# v6_config_io_16_17_21_22.net
KiCad netlist of a schematic drawn in Altium Designer
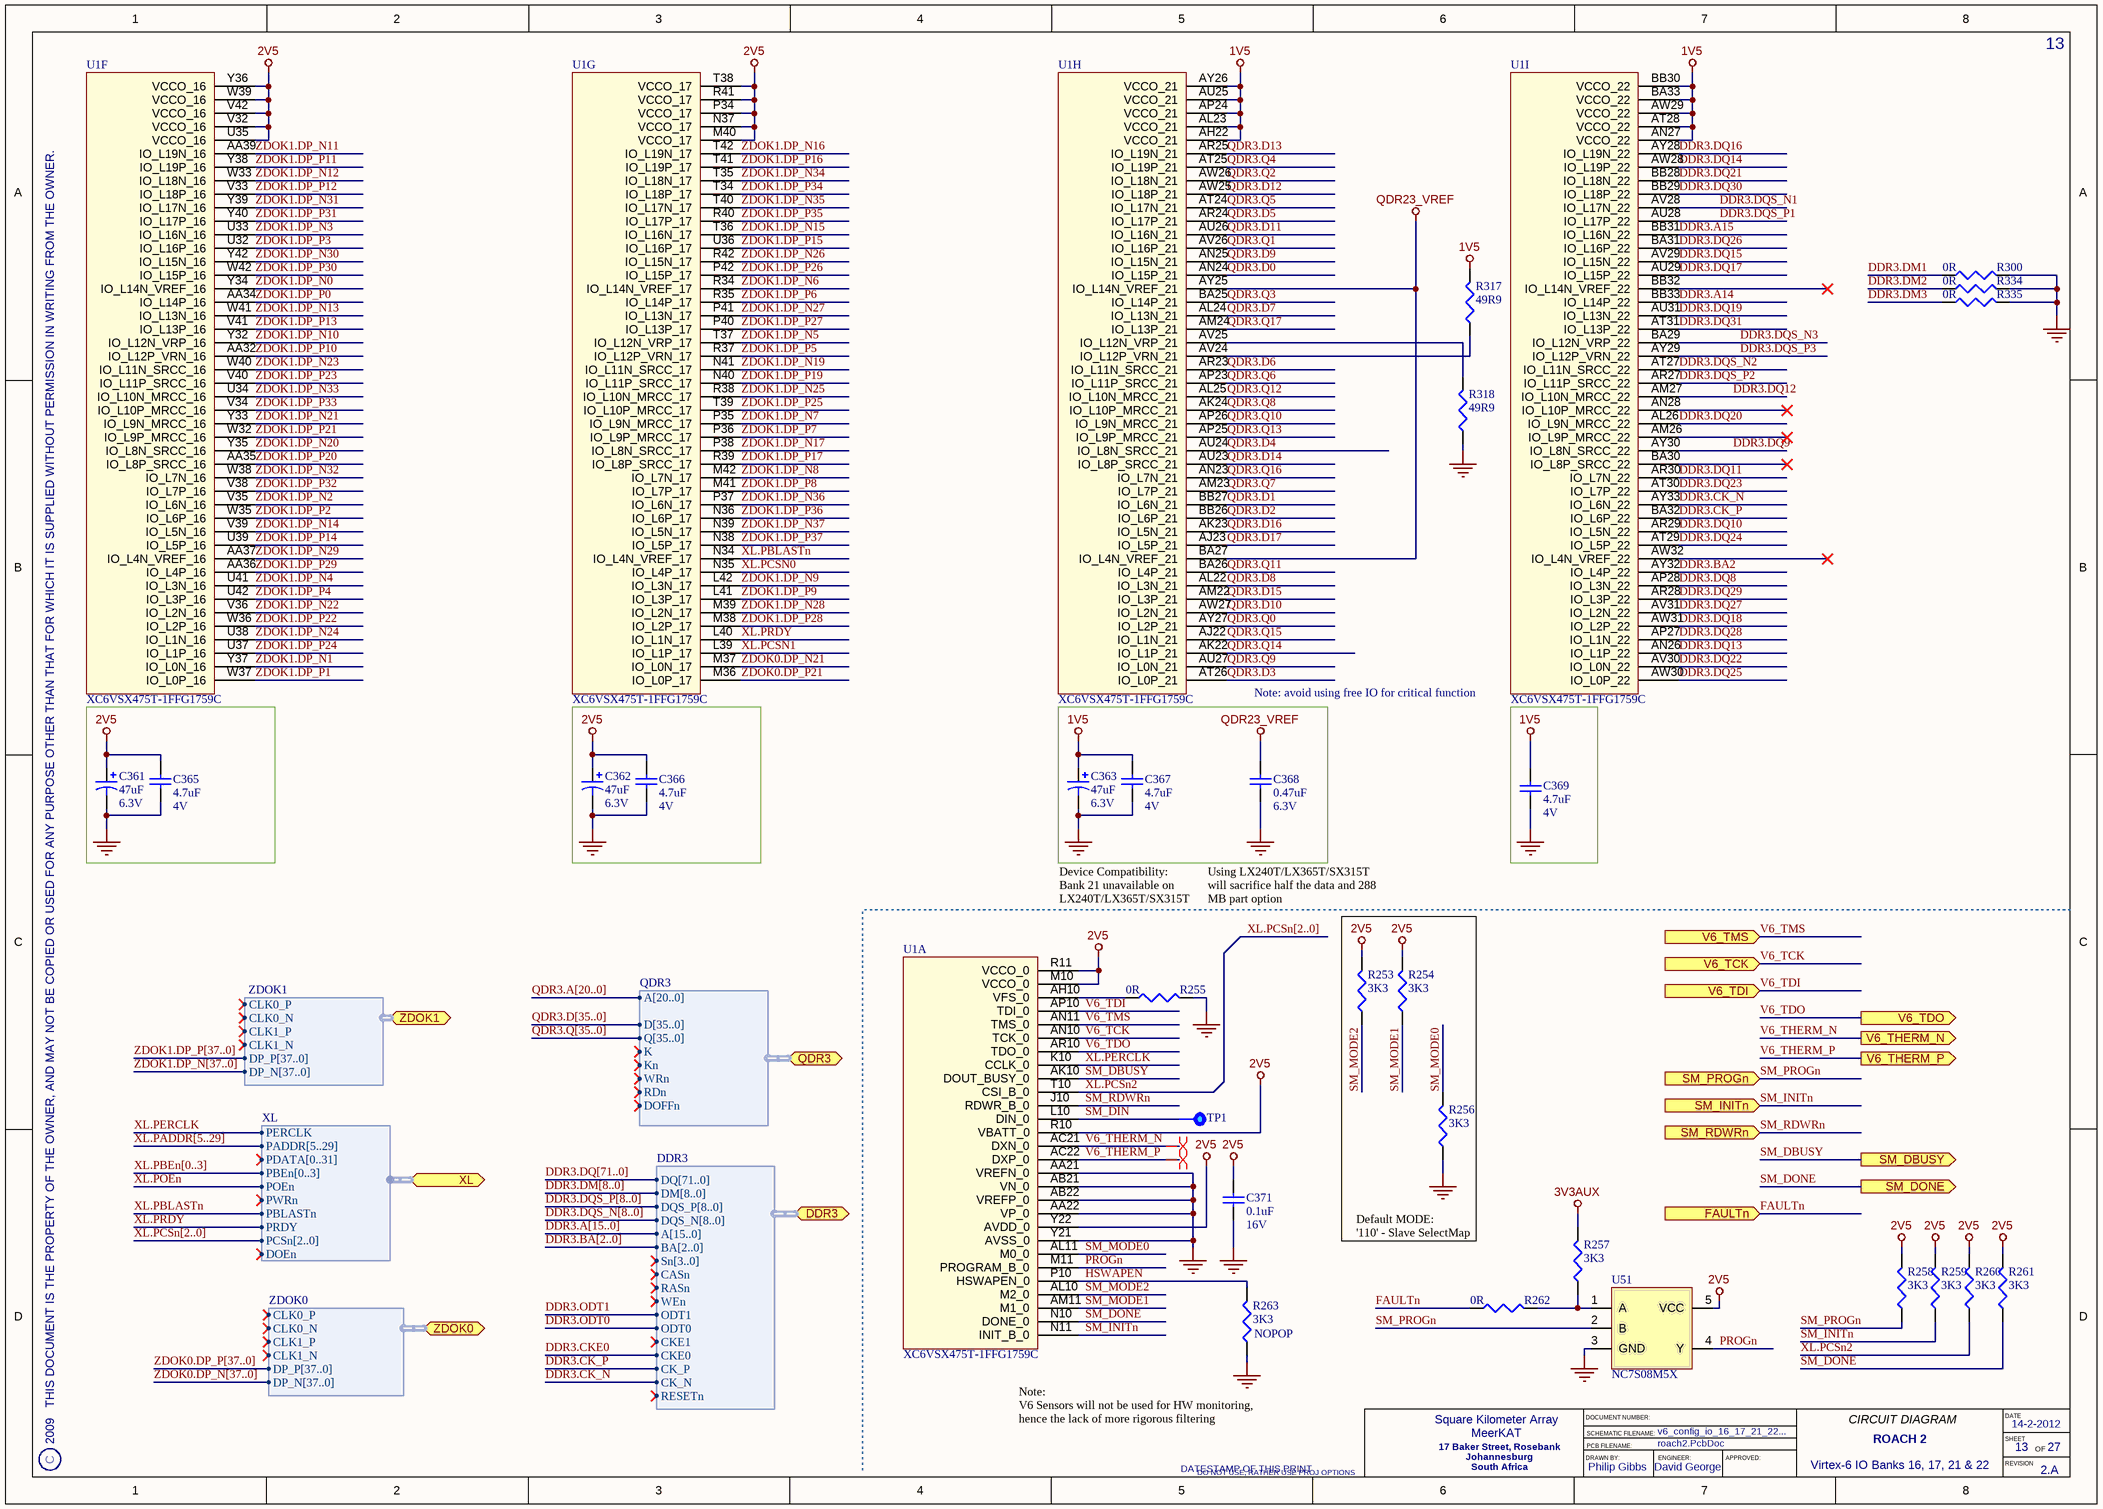
[diagram p0: v6_config_io_16_17_21_22.SchDoc]

(export (version "E")
  (design (tool "Eeschema 10.0.6"))
  (components
    (comp (ref "C361")
      (value "47uF")
      (footprint "CAPMP3528X120L")
      (description "47uF, Conductive Polymer Chip Capacitor")
      (fields
        (field (name "RATING") "6.3V")
        (field (name "MANUFACTURER") "KEMET")
        (field (name "PARTNUM") "T520T476M006ATE070")
      )
      (libsource (lib "altium_db") (part "CapPol"))
    )
    (comp (ref "C362")
      (value "47uF")
      (footprint "CAPMP3528X120L")
      (description "47uF, Conductive Polymer Chip Capacitor")
      (fields
        (field (name "RATING") "6.3V")
        (field (name "MANUFACTURER") "KEMET")
        (field (name "PARTNUM") "T520T476M006ATE070")
      )
      (libsource (lib "altium_db") (part "CapPol"))
    )
    (comp (ref "C363")
      (value "47uF")
      (footprint "CAPMP3528X120L")
      (description "47uF, Conductive Polymer Chip Capacitor")
      (fields
        (field (name "RATING") "6.3V")
        (field (name "MANUFACTURER") "KEMET")
        (field (name "PARTNUM") "T520T476M006ATE070")
      )
      (libsource (lib "altium_db") (part "CapPol"))
    )
    (comp (ref "C365")
      (value "4.7uF")
      (footprint "CAPC1005X60L")
      (description "4.7uF, Ceramic Capacitor")
      (fields
        (field (name "RATING") "4V")
        (field (name "MANUFACTURER") "MURATA")
        (field (name "PARTNUM") "AMK105BJ475MV-F")
      )
      (libsource (lib "altium_db") (part "CapStd"))
    )
    (comp (ref "C366")
      (value "4.7uF")
      (footprint "CAPC1005X60L")
      (description "4.7uF, Ceramic Capacitor")
      (fields
        (field (name "RATING") "4V")
        (field (name "MANUFACTURER") "MURATA")
        (field (name "PARTNUM") "AMK105BJ475MV-F")
      )
      (libsource (lib "altium_db") (part "CapStd"))
    )
    (comp (ref "C367")
      (value "4.7uF")
      (footprint "CAPC1005X60L")
      (description "4.7uF, Ceramic Capacitor")
      (fields
        (field (name "RATING") "4V")
        (field (name "MANUFACTURER") "MURATA")
        (field (name "PARTNUM") "AMK105BJ475MV-F")
      )
      (libsource (lib "altium_db") (part "CapStd"))
    )
    (comp (ref "C368")
      (value "0.47uF")
      (footprint "CAPC1005X55L")
      (description "0.47uF, Ceramic Capacitor")
      (fields
        (field (name "RATING") "6.3V")
        (field (name "MANUFACTURER") "MURATA")
        (field (name "PARTNUM") "GRM155R60J474KE19")
      )
      (libsource (lib "altium_db") (part "CapStd"))
    )
    (comp (ref "C369")
      (value "4.7uF")
      (footprint "CAPC1005X60L")
      (description "4.7uF, Ceramic Capacitor")
      (fields
        (field (name "RATING") "4V")
        (field (name "MANUFACTURER") "MURATA")
        (field (name "PARTNUM") "AMK105BJ475MV-F")
      )
      (libsource (lib "altium_db") (part "CapStd"))
    )
    (comp (ref "C371")
      (value "0.1uF")
      (footprint "CAPC1005X60L")
      (description "0.1uF, Ceramic Capacitor")
      (fields
        (field (name "RATING") "16V")
        (field (name "MANUFACTURER") "VENKEL")
        (field (name "PARTNUM") "C0402X7R160-104KN")
      )
      (libsource (lib "altium_db") (part "CapStd"))
    )
    (comp (ref "R253")
      (value "3K3")
      (footprint "RESC1005X40L")
      (description "3K3, 1.1mm x 0.5mm, Thick Film Resistor")
      (fields (field (name "MANUFACTURER") "ROYALOHM") (field (name "PARTNUM") "0402WGJ0332T1E"))
      (libsource (lib "altium_db") (part "ResStd"))
    )
    (comp (ref "R254")
      (value "3K3")
      (footprint "RESC1005X40L")
      (description "3K3, 1.1mm x 0.5mm, Thick Film Resistor")
      (fields (field (name "MANUFACTURER") "ROYALOHM") (field (name "PARTNUM") "0402WGJ0332T1E"))
      (libsource (lib "altium_db") (part "ResStd"))
    )
    (comp (ref "R255")
      (value "0R")
      (footprint "RESC1005X40L")
      (description "0R, 1.1mm x 0.5mm, Thick Film Resistor")
      (fields (field (name "MANUFACTURER") "ROYALOHM") (field (name "PARTNUM") "0402WG00000T1E"))
      (libsource (lib "altium_db") (part "ResStd"))
    )
    (comp (ref "R256")
      (value "3K3")
      (footprint "RESC1005X40L")
      (description "3K3, 1.1mm x 0.5mm, Thick Film Resistor")
      (fields (field (name "MANUFACTURER") "ROYALOHM") (field (name "PARTNUM") "0402WGJ0332T1E"))
      (libsource (lib "altium_db") (part "ResStd"))
    )
    (comp (ref "R257")
      (value "3K3")
      (footprint "RESC1005X40L")
      (description "3K3, 1.1mm x 0.5mm, Thick Film Resistor")
      (fields (field (name "MANUFACTURER") "ROYALOHM") (field (name "PARTNUM") "0402WGJ0332T1E"))
      (libsource (lib "altium_db") (part "ResStd"))
    )
    (comp (ref "R258")
      (value "3K3")
      (footprint "RESC1005X40L")
      (description "3K3, 1.1mm x 0.5mm, Thick Film Resistor")
      (fields (field (name "MANUFACTURER") "ROYALOHM") (field (name "PARTNUM") "0402WGJ0332T1E"))
      (libsource (lib "altium_db") (part "ResStd"))
    )
    (comp (ref "R259")
      (value "3K3")
      (footprint "RESC1005X40L")
      (description "3K3, 1.1mm x 0.5mm, Thick Film Resistor")
      (fields (field (name "MANUFACTURER") "ROYALOHM") (field (name "PARTNUM") "0402WGJ0332T1E"))
      (libsource (lib "altium_db") (part "ResStd"))
    )
    (comp (ref "R260")
      (value "3K3")
      (footprint "RESC1005X40L")
      (description "3K3, 1.1mm x 0.5mm, Thick Film Resistor")
      (fields (field (name "MANUFACTURER") "ROYALOHM") (field (name "PARTNUM") "0402WGJ0332T1E"))
      (libsource (lib "altium_db") (part "ResStd"))
    )
    (comp (ref "R261")
      (value "3K3")
      (footprint "RESC1005X40L")
      (description "3K3, 1.1mm x 0.5mm, Thick Film Resistor")
      (fields (field (name "MANUFACTURER") "ROYALOHM") (field (name "PARTNUM") "0402WGJ0332T1E"))
      (libsource (lib "altium_db") (part "ResStd"))
    )
    (comp (ref "R262")
      (value "0R")
      (footprint "RESC1005X40L")
      (description "0R, 1.1mm x 0.5mm, Thick Film Resistor")
      (fields (field (name "MANUFACTURER") "ROYALOHM") (field (name "PARTNUM") "0402WG00000T1E"))
      (libsource (lib "altium_db") (part "ResStd"))
    )
    (comp (ref "R263")
      (value "3K3")
      (footprint "RESC1005X40L")
      (description "3K3, 1.1mm x 0.5mm, Thick Film Resistor")
      (fields (field (name "MANUFACTURER") "ROYALOHM") (field (name "PARTNUM") "0402WGJ0332T1E"))
      (libsource (lib "altium_db") (part "ResStd"))
    )
    (comp (ref "R300")
      (value "0R")
      (footprint "RESC1005X40L")
      (description "0R, 1.1mm x 0.5mm, Thick Film Resistor")
      (fields (field (name "MANUFACTURER") "ROYALOHM") (field (name "PARTNUM") "0402WG00000T1E"))
      (libsource (lib "altium_db") (part "ResStd"))
    )
    (comp (ref "R317")
      (value "49R9")
      (footprint "RESC1005X40L")
      (description "49R9, 1.1mm x 0.5mm, Thick Film Resistor")
      (fields (field (name "MANUFACTURER") "ROYALOHM") (field (name "PARTNUM") "0402WGF499JT1E"))
      (libsource (lib "altium_db") (part "ResStd"))
    )
    (comp (ref "R318")
      (value "49R9")
      (footprint "RESC1005X40L")
      (description "49R9, 1.1mm x 0.5mm, Thick Film Resistor")
      (fields (field (name "MANUFACTURER") "ROYALOHM") (field (name "PARTNUM") "0402WGF499JT1E"))
      (libsource (lib "altium_db") (part "ResStd"))
    )
    (comp (ref "R334")
      (value "0R")
      (footprint "RESC1005X40L")
      (description "0R, 1.1mm x 0.5mm, Thick Film Resistor")
      (fields (field (name "MANUFACTURER") "ROYALOHM") (field (name "PARTNUM") "0402WG00000T1E"))
      (libsource (lib "altium_db") (part "ResStd"))
    )
    (comp (ref "R335")
      (value "0R")
      (footprint "RESC1005X40L")
      (description "0R, 1.1mm x 0.5mm, Thick Film Resistor")
      (fields (field (name "MANUFACTURER") "ROYALOHM") (field (name "PARTNUM") "0402WG00000T1E"))
      (libsource (lib "altium_db") (part "ResStd"))
    )
    (comp (ref "TP1")
      (value "Testpoint")
      (footprint "TP100")
      (description "1mm Diameter, through-hole, Circular Test-point")
      (libsource (lib "altium_db") (part "Testpoint"))
    )
    (comp (ref "U1")
      (value "XC6VSX475T-1FFG1759C")
      (footprint "FFG1759")
      (description "Virtex-6 475SXT 1760-pin FPGA")
      (fields (field (name "MANUFACTURER") "Xilinx"))
      (libsource (lib "altium_db") (part "XC6VSX475T-1FFG1759C"))
    )
    (comp (ref "U51")
      (value "NC7S08M5X")
      (footprint "SOT23-5")
      (description "TinyLogic® HS 2-Input AND Gate")
      (fields (field (name "MANUFACTURER") "Fairchild Semiconductor"))
      (libsource (lib "altium_db") (part "NC7S08"))
    )
  )
  (nets
    (net (code "185") (name "/DDR3.A14") (class "Default")
      (node (ref "U1") (pin "BB33") (pinfunction "IO_L14P_22_BB33") (pintype "passive"))
    )
    (net (code "186") (name "/DDR3.A15") (class "Default")
      (node (ref "U1") (pin "BB31") (pinfunction "IO_L16N_22_BB31") (pintype "passive"))
    )
    (net (code "188") (name "/DDR3.BA2") (class "Default")
      (node (ref "U1") (pin "AY32") (pinfunction "IO_L4P_22_AY32") (pintype "passive"))
    )
    (net (code "191") (name "/DDR3.CK_N") (class "Default")
      (node (ref "U1") (pin "AY33") (pinfunction "IO_L6N_22_AY33") (pintype "passive"))
    )
    (net (code "192") (name "/DDR3.CK_P") (class "Default")
      (node (ref "U1") (pin "BA32") (pinfunction "IO_L6P_22_BA32") (pintype "passive"))
    )
    (net (code "193") (name "/DDR3.DM1") (class "Default")
      (node (ref "R300") (pin "1") (pinfunction "1_1") (pintype "passive"))
    )
    (net (code "194") (name "/DDR3.DM2") (class "Default")
      (node (ref "R334") (pin "1") (pinfunction "1_1") (pintype "passive"))
    )
    (net (code "195") (name "/DDR3.DM3") (class "Default")
      (node (ref "R335") (pin "1") (pinfunction "1_1") (pintype "passive"))
    )
    (net (code "197") (name "/DDR3.DQ8") (class "Default")
      (node (ref "U1") (pin "AP28") (pinfunction "IO_L3N_22_AP28") (pintype "passive"))
    )
    (net (code "198") (name "/DDR3.DQ9") (class "Default")
      (node (ref "U1") (pin "AY30") (pinfunction "IO_L8N_SRCC_22_AY30") (pintype "passive"))
    )
    (net (code "199") (name "/DDR3.DQ10") (class "Default")
      (node (ref "U1") (pin "AR29") (pinfunction "IO_L5N_22_AR29") (pintype "passive"))
    )
    (net (code "200") (name "/DDR3.DQ11") (class "Default")
      (node (ref "U1") (pin "AR30") (pinfunction "IO_L7N_22_AR30") (pintype "passive"))
    )
    (net (code "201") (name "/DDR3.DQ12") (class "Default")
      (node (ref "U1") (pin "AM27") (pinfunction "IO_L10N_MRCC_22_AM27") (pintype "passive"))
    )
    (net (code "202") (name "/DDR3.DQ13") (class "Default")
      (node (ref "U1") (pin "AN26") (pinfunction "IO_L1P_22_AN26") (pintype "passive"))
    )
    (net (code "203") (name "/DDR3.DQ14") (class "Default")
      (node (ref "U1") (pin "AW28") (pinfunction "IO_L19P_22_AW28") (pintype "passive"))
    )
    (net (code "204") (name "/DDR3.DQ15") (class "Default")
      (node (ref "U1") (pin "AV29") (pinfunction "IO_L15N_22_AV29") (pintype "passive"))
    )
    (net (code "205") (name "/DDR3.DQ16") (class "Default")
      (node (ref "U1") (pin "AY28") (pinfunction "IO_L19N_22_AY28") (pintype "passive"))
    )
    (net (code "206") (name "/DDR3.DQ17") (class "Default")
      (node (ref "U1") (pin "AU29") (pinfunction "IO_L15P_22_AU29") (pintype "passive"))
    )
    (net (code "207") (name "/DDR3.DQ18") (class "Default")
      (node (ref "U1") (pin "AW31") (pinfunction "IO_L2P_22_AW31") (pintype "passive"))
    )
    (net (code "208") (name "/DDR3.DQ19") (class "Default")
      (node (ref "U1") (pin "AU31") (pinfunction "IO_L13N_22_AU31") (pintype "passive"))
    )
    (net (code "209") (name "/DDR3.DQ20") (class "Default")
      (node (ref "U1") (pin "AL26") (pinfunction "IO_L9N_MRCC_22_AL26") (pintype "passive"))
    )
    (net (code "210") (name "/DDR3.DQ21") (class "Default")
      (node (ref "U1") (pin "BB28") (pinfunction "IO_L18N_22_BB28") (pintype "passive"))
    )
    (net (code "211") (name "/DDR3.DQ22") (class "Default")
      (node (ref "U1") (pin "AV30") (pinfunction "IO_L0N_22_AV30") (pintype "passive"))
    )
    (net (code "212") (name "/DDR3.DQ23") (class "Default")
      (node (ref "U1") (pin "AT30") (pinfunction "IO_L7P_22_AT30") (pintype "passive"))
    )
    (net (code "213") (name "/DDR3.DQ24") (class "Default")
      (node (ref "U1") (pin "AT29") (pinfunction "IO_L5P_22_AT29") (pintype "passive"))
    )
    (net (code "214") (name "/DDR3.DQ25") (class "Default")
      (node (ref "U1") (pin "AW30") (pinfunction "IO_L0P_22_AW30") (pintype "passive"))
    )
    (net (code "215") (name "/DDR3.DQ26") (class "Default")
      (node (ref "U1") (pin "BA31") (pinfunction "IO_L16P_22_BA31") (pintype "passive"))
    )
    (net (code "216") (name "/DDR3.DQ27") (class "Default")
      (node (ref "U1") (pin "AV31") (pinfunction "IO_L2N_22_AV31") (pintype "passive"))
    )
    (net (code "217") (name "/DDR3.DQ28") (class "Default")
      (node (ref "U1") (pin "AP27") (pinfunction "IO_L1N_22_AP27") (pintype "passive"))
    )
    (net (code "218") (name "/DDR3.DQ29") (class "Default")
      (node (ref "U1") (pin "AR28") (pinfunction "IO_L3P_22_AR28") (pintype "passive"))
    )
    (net (code "219") (name "/DDR3.DQ30") (class "Default")
      (node (ref "U1") (pin "BB29") (pinfunction "IO_L18P_22_BB29") (pintype "passive"))
    )
    (net (code "220") (name "/DDR3.DQ31") (class "Default")
      (node (ref "U1") (pin "AT31") (pinfunction "IO_L13P_22_AT31") (pintype "passive"))
    )
    (net (code "221") (name "/DDR3.DQS_N1") (class "Default")
      (node (ref "U1") (pin "AV28") (pinfunction "IO_L17N_22_AV28") (pintype "passive"))
    )
    (net (code "222") (name "/DDR3.DQS_N2") (class "Default")
      (node (ref "U1") (pin "AT27") (pinfunction "IO_L11N_SRCC_22_AT27") (pintype "passive"))
    )
    (net (code "223") (name "/DDR3.DQS_N3") (class "Default")
      (node (ref "U1") (pin "BA29") (pinfunction "IO_L12N_VRP_22_BA29") (pintype "passive"))
    )
    (net (code "225") (name "/DDR3.DQS_P1") (class "Default")
      (node (ref "U1") (pin "AU28") (pinfunction "IO_L17P_22_AU28") (pintype "passive"))
    )
    (net (code "226") (name "/DDR3.DQS_P2") (class "Default")
      (node (ref "U1") (pin "AR27") (pinfunction "IO_L11P_SRCC_22_AR27") (pintype "passive"))
    )
    (net (code "227") (name "/DDR3.DQS_P3") (class "Default")
      (node (ref "U1") (pin "AY29") (pinfunction "IO_L12P_VRN_22_AY29") (pintype "passive"))
    )
    (net (code "232") (name "/FAULTn") (class "Default")
      (node (ref "R262") (pin "1") (pinfunction "1_1") (pintype "passive"))
    )
    (net (code "233") (name "/HSWAPEN") (class "Default")
      (node (ref "R263") (pin "2") (pinfunction "2_2") (pintype "passive"))
      (node (ref "U1") (pin "P10") (pinfunction "HSWAPEN_0_P10") (pintype "passive"))
    )
    (net (code "234") (name "/PROGn") (class "Default")
      (node (ref "U1") (pin "M11") (pinfunction "PROGRAM_B_0_M11") (pintype "passive"))
      (node (ref "U51") (pin "4") (pinfunction "Y_4") (pintype "passive"))
    )
    (net (code "236") (name "/QDR3.D0") (class "Default")
      (node (ref "U1") (pin "AN24") (pinfunction "IO_L15P_21_AN24") (pintype "passive"))
    )
    (net (code "237") (name "/QDR3.D1") (class "Default")
      (node (ref "U1") (pin "BB27") (pinfunction "IO_L6N_21_BB27") (pintype "passive"))
    )
    (net (code "238") (name "/QDR3.D2") (class "Default")
      (node (ref "U1") (pin "BB26") (pinfunction "IO_L6P_21_BB26") (pintype "passive"))
    )
    (net (code "239") (name "/QDR3.D3") (class "Default")
      (node (ref "U1") (pin "AT26") (pinfunction "IO_L0P_21_AT26") (pintype "passive"))
    )
    (net (code "240") (name "/QDR3.D4") (class "Default")
      (node (ref "U1") (pin "AU24") (pinfunction "IO_L8N_SRCC_21_AU24") (pintype "passive"))
    )
    (net (code "241") (name "/QDR3.D5") (class "Default")
      (node (ref "U1") (pin "AR24") (pinfunction "IO_L17P_21_AR24") (pintype "passive"))
    )
    (net (code "242") (name "/QDR3.D6") (class "Default")
      (node (ref "U1") (pin "AR23") (pinfunction "IO_L11N_SRCC_21_AR23") (pintype "passive"))
    )
    (net (code "243") (name "/QDR3.D7") (class "Default")
      (node (ref "U1") (pin "AL24") (pinfunction "IO_L13N_21_AL24") (pintype "passive"))
    )
    (net (code "244") (name "/QDR3.D8") (class "Default")
      (node (ref "U1") (pin "AL22") (pinfunction "IO_L3N_21_AL22") (pintype "passive"))
    )
    (net (code "245") (name "/QDR3.D9") (class "Default")
      (node (ref "U1") (pin "AN25") (pinfunction "IO_L15N_21_AN25") (pintype "passive"))
    )
    (net (code "246") (name "/QDR3.D10") (class "Default")
      (node (ref "U1") (pin "AW27") (pinfunction "IO_L2N_21_AW27") (pintype "passive"))
    )
    (net (code "247") (name "/QDR3.D11") (class "Default")
      (node (ref "U1") (pin "AU26") (pinfunction "IO_L16N_21_AU26") (pintype "passive"))
    )
    (net (code "248") (name "/QDR3.D12") (class "Default")
      (node (ref "U1") (pin "AW25") (pinfunction "IO_L18P_21_AW25") (pintype "passive"))
    )
    (net (code "249") (name "/QDR3.D13") (class "Default")
      (node (ref "U1") (pin "AR25") (pinfunction "IO_L19N_21_AR25") (pintype "passive"))
    )
    (net (code "250") (name "/QDR3.D14") (class "Default")
      (node (ref "U1") (pin "AU23") (pinfunction "IO_L8P_SRCC_21_AU23") (pintype "passive"))
    )
    (net (code "251") (name "/QDR3.D15") (class "Default")
      (node (ref "U1") (pin "AM22") (pinfunction "IO_L3P_21_AM22") (pintype "passive"))
    )
    (net (code "252") (name "/QDR3.D16") (class "Default")
      (node (ref "U1") (pin "AK23") (pinfunction "IO_L5N_21_AK23") (pintype "passive"))
    )
    (net (code "253") (name "/QDR3.D17") (class "Default")
      (node (ref "U1") (pin "AJ23") (pinfunction "IO_L5P_21_AJ23") (pintype "passive"))
    )
    (net (code "255") (name "/QDR3.Q0") (class "Default")
      (node (ref "U1") (pin "AY27") (pinfunction "IO_L2P_21_AY27") (pintype "passive"))
    )
    (net (code "256") (name "/QDR3.Q1") (class "Default")
      (node (ref "U1") (pin "AV26") (pinfunction "IO_L16P_21_AV26") (pintype "passive"))
    )
    (net (code "257") (name "/QDR3.Q2") (class "Default")
      (node (ref "U1") (pin "AW26") (pinfunction "IO_L18N_21_AW26") (pintype "passive"))
    )
    (net (code "258") (name "/QDR3.Q3") (class "Default")
      (node (ref "U1") (pin "BA25") (pinfunction "IO_L14P_21_BA25") (pintype "passive"))
    )
    (net (code "259") (name "/QDR3.Q4") (class "Default")
      (node (ref "U1") (pin "AT25") (pinfunction "IO_L19P_21_AT25") (pintype "passive"))
    )
    (net (code "260") (name "/QDR3.Q5") (class "Default")
      (node (ref "U1") (pin "AT24") (pinfunction "IO_L17N_21_AT24") (pintype "passive"))
    )
    (net (code "261") (name "/QDR3.Q6") (class "Default")
      (node (ref "U1") (pin "AP23") (pinfunction "IO_L11P_SRCC_21_AP23") (pintype "passive"))
    )
    (net (code "262") (name "/QDR3.Q7") (class "Default")
      (node (ref "U1") (pin "AM23") (pinfunction "IO_L7P_21_AM23") (pintype "passive"))
    )
    (net (code "263") (name "/QDR3.Q8") (class "Default")
      (node (ref "U1") (pin "AK24") (pinfunction "IO_L10P_MRCC_21_AK24") (pintype "passive"))
    )
    (net (code "264") (name "/QDR3.Q9") (class "Default")
      (node (ref "U1") (pin "AU27") (pinfunction "IO_L0N_21_AU27") (pintype "passive"))
    )
    (net (code "265") (name "/QDR3.Q10") (class "Default")
      (node (ref "U1") (pin "AP26") (pinfunction "IO_L9N_MRCC_21_AP26") (pintype "passive"))
    )
    (net (code "266") (name "/QDR3.Q11") (class "Default")
      (node (ref "U1") (pin "BA26") (pinfunction "IO_L4P_21_BA26") (pintype "passive"))
    )
    (net (code "267") (name "/QDR3.Q12") (class "Default")
      (node (ref "U1") (pin "AL25") (pinfunction "IO_L10N_MRCC_21_AL25") (pintype "passive"))
    )
    (net (code "268") (name "/QDR3.Q13") (class "Default")
      (node (ref "U1") (pin "AP25") (pinfunction "IO_L9P_MRCC_21_AP25") (pintype "passive"))
    )
    (net (code "269") (name "/QDR3.Q14") (class "Default")
      (node (ref "U1") (pin "AK22") (pinfunction "IO_L1P_21_AK22") (pintype "passive"))
    )
    (net (code "270") (name "/QDR3.Q15") (class "Default")
      (node (ref "U1") (pin "AJ22") (pinfunction "IO_L1N_21_AJ22") (pintype "passive"))
    )
    (net (code "271") (name "/QDR3.Q16") (class "Default")
      (node (ref "U1") (pin "AN23") (pinfunction "IO_L7N_21_AN23") (pintype "passive"))
    )
    (net (code "272") (name "/QDR3.Q17") (class "Default")
      (node (ref "U1") (pin "AM24") (pinfunction "IO_L13P_21_AM24") (pintype "passive"))
    )
    (net (code "274") (name "/SM_DBUSY") (class "Default")
      (node (ref "U1") (pin "AK10") (pinfunction "DOUT_BUSY_0_AK10") (pintype "passive"))
    )
    (net (code "275") (name "/SM_DIN") (class "Default")
      (node (ref "TP1") (pin "1") (pinfunction "1_1") (pintype "passive"))
      (node (ref "U1") (pin "L10") (pinfunction "DIN_0_L10") (pintype "passive"))
    )
    (net (code "276") (name "/SM_DONE") (class "Default")
      (node (ref "R261") (pin "1") (pinfunction "1_1") (pintype "passive"))
      (node (ref "U1") (pin "N10") (pinfunction "DONE_0_N10") (pintype "passive"))
    )
    (net (code "277") (name "/SM_INITn") (class "Default")
      (node (ref "R259") (pin "1") (pinfunction "1_1") (pintype "passive"))
      (node (ref "U1") (pin "N11") (pinfunction "INIT_B_0_N11") (pintype "passive"))
    )
    (net (code "278") (name "/SM_MODE0") (class "Default")
      (node (ref "R256") (pin "2") (pinfunction "2_2") (pintype "passive"))
      (node (ref "U1") (pin "AL11") (pinfunction "M0_0_AL11") (pintype "passive"))
    )
    (net (code "279") (name "/SM_MODE1") (class "Default")
      (node (ref "R254") (pin "1") (pinfunction "1_1") (pintype "passive"))
      (node (ref "U1") (pin "AM11") (pinfunction "M1_0_AM11") (pintype "passive"))
    )
    (net (code "280") (name "/SM_MODE2") (class "Default")
      (node (ref "R253") (pin "1") (pinfunction "1_1") (pintype "passive"))
      (node (ref "U1") (pin "AL10") (pinfunction "M2_0_AL10") (pintype "passive"))
    )
    (net (code "281") (name "/SM_PROGn") (class "Default")
      (node (ref "R258") (pin "1") (pinfunction "1_1") (pintype "passive"))
      (node (ref "U51") (pin "2") (pinfunction "B_2") (pintype "passive"))
    )
    (net (code "282") (name "/SM_RDWRn") (class "Default")
      (node (ref "U1") (pin "J10") (pinfunction "RDWR_B_0_J10") (pintype "passive"))
    )
    (net (code "283") (name "/V6_TCK") (class "Default")
      (node (ref "U1") (pin "AN10") (pinfunction "TCK_0_AN10") (pintype "passive"))
    )
    (net (code "284") (name "/V6_TDI") (class "Default")
      (node (ref "U1") (pin "AP10") (pinfunction "TDI_0_AP10") (pintype "passive"))
    )
    (net (code "285") (name "/V6_TDO") (class "Default")
      (node (ref "U1") (pin "AR10") (pinfunction "TDO_0_AR10") (pintype "passive"))
    )
    (net (code "286") (name "/V6_THERM_N") (class "Default")
      (node (ref "U1") (pin "AC21") (pinfunction "DXN_0_AC21") (pintype "passive"))
    )
    (net (code "287") (name "/V6_THERM_P") (class "Default")
      (node (ref "U1") (pin "AC22") (pinfunction "DXP_0_AC22") (pintype "passive"))
    )
    (net (code "288") (name "/V6_TMS") (class "Default")
      (node (ref "U1") (pin "AN11") (pinfunction "TMS_0_AN11") (pintype "passive"))
    )
    (net (code "291") (name "/XL.PBLASTn") (class "Default")
      (node (ref "U1") (pin "N34") (pinfunction "IO_L4N_VREF_17_N34") (pintype "passive"))
    )
    (net (code "292") (name "/XL.PCSN0") (class "Default")
      (node (ref "U1") (pin "N35") (pinfunction "IO_L4P_17_N35") (pintype "passive"))
    )
    (net (code "293") (name "/XL.PCSN1") (class "Default")
      (node (ref "U1") (pin "L39") (pinfunction "IO_L1P_17_L39") (pintype "passive"))
    )
    (net (code "294") (name "/XL.PCSn2") (class "Default")
      (node (ref "R260") (pin "1") (pinfunction "1_1") (pintype "passive"))
      (node (ref "U1") (pin "T10") (pinfunction "CSI_B_0_T10") (pintype "passive"))
    )
    (net (code "296") (name "/XL.PERCLK") (class "Default")
      (node (ref "U1") (pin "K10") (pinfunction "CCLK_0_K10") (pintype "passive"))
    )
    (net (code "298") (name "/XL.PRDY") (class "Default")
      (node (ref "U1") (pin "L40") (pinfunction "IO_L1N_17_L40") (pintype "passive"))
    )
    (net (code "300") (name "/ZDOK0.DP_N21") (class "Default")
      (node (ref "U1") (pin "M37") (pinfunction "IO_L0N_17_M37") (pintype "passive"))
    )
    (net (code "302") (name "/ZDOK0.DP_P21") (class "Default")
      (node (ref "U1") (pin "M36") (pinfunction "IO_L0P_17_M36") (pintype "passive"))
    )
    (net (code "304") (name "/ZDOK1.DP_N0") (class "Default")
      (node (ref "U1") (pin "Y34") (pinfunction "IO_L14N_VREF_16_Y34") (pintype "passive"))
    )
    (net (code "305") (name "/ZDOK1.DP_N1") (class "Default")
      (node (ref "U1") (pin "Y37") (pinfunction "IO_L0N_16_Y37") (pintype "passive"))
    )
    (net (code "306") (name "/ZDOK1.DP_N2") (class "Default")
      (node (ref "U1") (pin "V35") (pinfunction "IO_L6N_16_V35") (pintype "passive"))
    )
    (net (code "307") (name "/ZDOK1.DP_N3") (class "Default")
      (node (ref "U1") (pin "U33") (pinfunction "IO_L16N_16_U33") (pintype "passive"))
    )
    (net (code "308") (name "/ZDOK1.DP_N4") (class "Default")
      (node (ref "U1") (pin "U41") (pinfunction "IO_L3N_16_U41") (pintype "passive"))
    )
    (net (code "309") (name "/ZDOK1.DP_N5") (class "Default")
      (node (ref "U1") (pin "T37") (pinfunction "IO_L12N_VRP_17_T37") (pintype "passive"))
    )
    (net (code "310") (name "/ZDOK1.DP_N6") (class "Default")
      (node (ref "U1") (pin "R34") (pinfunction "IO_L14N_VREF_17_R34") (pintype "passive"))
    )
    (net (code "311") (name "/ZDOK1.DP_N7") (class "Default")
      (node (ref "U1") (pin "P35") (pinfunction "IO_L9N_MRCC_17_P35") (pintype "passive"))
    )
    (net (code "312") (name "/ZDOK1.DP_N8") (class "Default")
      (node (ref "U1") (pin "M42") (pinfunction "IO_L7N_17_M42") (pintype "passive"))
    )
    (net (code "313") (name "/ZDOK1.DP_N9") (class "Default")
      (node (ref "U1") (pin "L42") (pinfunction "IO_L3N_17_L42") (pintype "passive"))
    )
    (net (code "314") (name "/ZDOK1.DP_N10") (class "Default")
      (node (ref "U1") (pin "Y32") (pinfunction "IO_L12N_VRP_16_Y32") (pintype "passive"))
    )
    (net (code "315") (name "/ZDOK1.DP_N11") (class "Default")
      (node (ref "U1") (pin "AA39") (pinfunction "IO_L19N_16_AA39") (pintype "passive"))
    )
    (net (code "316") (name "/ZDOK1.DP_N12") (class "Default")
      (node (ref "U1") (pin "W33") (pinfunction "IO_L18N_16_W33") (pintype "passive"))
    )
    (net (code "317") (name "/ZDOK1.DP_N13") (class "Default")
      (node (ref "U1") (pin "W41") (pinfunction "IO_L13N_16_W41") (pintype "passive"))
    )
    (net (code "318") (name "/ZDOK1.DP_N14") (class "Default")
      (node (ref "U1") (pin "V39") (pinfunction "IO_L5N_16_V39") (pintype "passive"))
    )
    (net (code "319") (name "/ZDOK1.DP_N15") (class "Default")
      (node (ref "U1") (pin "T36") (pinfunction "IO_L16N_17_T36") (pintype "passive"))
    )
    (net (code "320") (name "/ZDOK1.DP_N16") (class "Default")
      (node (ref "U1") (pin "T42") (pinfunction "IO_L19N_17_T42") (pintype "passive"))
    )
    (net (code "321") (name "/ZDOK1.DP_N17") (class "Default")
      (node (ref "U1") (pin "P38") (pinfunction "IO_L8N_SRCC_17_P38") (pintype "passive"))
    )
    (net (code "322") (name "/ZDOK1.DP_N19") (class "Default")
      (node (ref "U1") (pin "N41") (pinfunction "IO_L11N_SRCC_17_N41") (pintype "passive"))
    )
    (net (code "323") (name "/ZDOK1.DP_N20") (class "Default")
      (node (ref "U1") (pin "Y35") (pinfunction "IO_L8N_SRCC_16_Y35") (pintype "passive"))
    )
    (net (code "324") (name "/ZDOK1.DP_N21") (class "Default")
      (node (ref "U1") (pin "Y33") (pinfunction "IO_L9N_MRCC_16_Y33") (pintype "passive"))
    )
    (net (code "325") (name "/ZDOK1.DP_N22") (class "Default")
      (node (ref "U1") (pin "V36") (pinfunction "IO_L2N_16_V36") (pintype "passive"))
    )
    (net (code "326") (name "/ZDOK1.DP_N23") (class "Default")
      (node (ref "U1") (pin "W40") (pinfunction "IO_L11N_SRCC_16_W40") (pintype "passive"))
    )
    (net (code "327") (name "/ZDOK1.DP_N24") (class "Default")
      (node (ref "U1") (pin "U38") (pinfunction "IO_L1N_16_U38") (pintype "passive"))
    )
    (net (code "328") (name "/ZDOK1.DP_N25") (class "Default")
      (node (ref "U1") (pin "R38") (pinfunction "IO_L10N_MRCC_17_R38") (pintype "passive"))
    )
    (net (code "329") (name "/ZDOK1.DP_N26") (class "Default")
      (node (ref "U1") (pin "R42") (pinfunction "IO_L15N_17_R42") (pintype "passive"))
    )
    (net (code "330") (name "/ZDOK1.DP_N27") (class "Default")
      (node (ref "U1") (pin "P41") (pinfunction "IO_L13N_17_P41") (pintype "passive"))
    )
    (net (code "331") (name "/ZDOK1.DP_N28") (class "Default")
      (node (ref "U1") (pin "M39") (pinfunction "IO_L2N_17_M39") (pintype "passive"))
    )
    (net (code "332") (name "/ZDOK1.DP_N29") (class "Default")
      (node (ref "U1") (pin "AA37") (pinfunction "IO_L4N_VREF_16_AA37") (pintype "passive"))
    )
    (net (code "333") (name "/ZDOK1.DP_N30") (class "Default")
      (node (ref "U1") (pin "Y42") (pinfunction "IO_L15N_16_Y42") (pintype "passive"))
    )
    (net (code "334") (name "/ZDOK1.DP_N31") (class "Default")
      (node (ref "U1") (pin "Y39") (pinfunction "IO_L17N_16_Y39") (pintype "passive"))
    )
    (net (code "335") (name "/ZDOK1.DP_N32") (class "Default")
      (node (ref "U1") (pin "W38") (pinfunction "IO_L7N_16_W38") (pintype "passive"))
    )
    (net (code "336") (name "/ZDOK1.DP_N33") (class "Default")
      (node (ref "U1") (pin "U34") (pinfunction "IO_L10N_MRCC_16_U34") (pintype "passive"))
    )
    (net (code "337") (name "/ZDOK1.DP_N34") (class "Default")
      (node (ref "U1") (pin "T35") (pinfunction "IO_L18N_17_T35") (pintype "passive"))
    )
    (net (code "338") (name "/ZDOK1.DP_N35") (class "Default")
      (node (ref "U1") (pin "T40") (pinfunction "IO_L17N_17_T40") (pintype "passive"))
    )
    (net (code "339") (name "/ZDOK1.DP_N36") (class "Default")
      (node (ref "U1") (pin "P37") (pinfunction "IO_L6N_17_P37") (pintype "passive"))
    )
    (net (code "340") (name "/ZDOK1.DP_N37") (class "Default")
      (node (ref "U1") (pin "N39") (pinfunction "IO_L5N_17_N39") (pintype "passive"))
    )
    (net (code "341") (name "/ZDOK1.DP_P0") (class "Default")
      (node (ref "U1") (pin "AA34") (pinfunction "IO_L14P_16_AA34") (pintype "passive"))
    )
    (net (code "342") (name "/ZDOK1.DP_P1") (class "Default")
      (node (ref "U1") (pin "W37") (pinfunction "IO_L0P_16_W37") (pintype "passive"))
    )
    (net (code "343") (name "/ZDOK1.DP_P2") (class "Default")
      (node (ref "U1") (pin "W35") (pinfunction "IO_L6P_16_W35") (pintype "passive"))
    )
    (net (code "344") (name "/ZDOK1.DP_P3") (class "Default")
      (node (ref "U1") (pin "U32") (pinfunction "IO_L16P_16_U32") (pintype "passive"))
    )
    (net (code "345") (name "/ZDOK1.DP_P4") (class "Default")
      (node (ref "U1") (pin "U42") (pinfunction "IO_L3P_16_U42") (pintype "passive"))
    )
    (net (code "346") (name "/ZDOK1.DP_P5") (class "Default")
      (node (ref "U1") (pin "R37") (pinfunction "IO_L12P_VRN_17_R37") (pintype "passive"))
    )
    (net (code "347") (name "/ZDOK1.DP_P6") (class "Default")
      (node (ref "U1") (pin "R35") (pinfunction "IO_L14P_17_R35") (pintype "passive"))
    )
    (net (code "348") (name "/ZDOK1.DP_P7") (class "Default")
      (node (ref "U1") (pin "P36") (pinfunction "IO_L9P_MRCC_17_P36") (pintype "passive"))
    )
    (net (code "349") (name "/ZDOK1.DP_P8") (class "Default")
      (node (ref "U1") (pin "M41") (pinfunction "IO_L7P_17_M41") (pintype "passive"))
    )
    (net (code "350") (name "/ZDOK1.DP_P9") (class "Default")
      (node (ref "U1") (pin "L41") (pinfunction "IO_L3P_17_L41") (pintype "passive"))
    )
    (net (code "351") (name "/ZDOK1.DP_P10") (class "Default")
      (node (ref "U1") (pin "AA32") (pinfunction "IO_L12P_VRN_16_AA32") (pintype "passive"))
    )
    (net (code "352") (name "/ZDOK1.DP_P11") (class "Default")
      (node (ref "U1") (pin "Y38") (pinfunction "IO_L19P_16_Y38") (pintype "passive"))
    )
    (net (code "353") (name "/ZDOK1.DP_P12") (class "Default")
      (node (ref "U1") (pin "V33") (pinfunction "IO_L18P_16_V33") (pintype "passive"))
    )
    (net (code "354") (name "/ZDOK1.DP_P13") (class "Default")
      (node (ref "U1") (pin "V41") (pinfunction "IO_L13P_16_V41") (pintype "passive"))
    )
    (net (code "355") (name "/ZDOK1.DP_P14") (class "Default")
      (node (ref "U1") (pin "U39") (pinfunction "IO_L5P_16_U39") (pintype "passive"))
    )
    (net (code "356") (name "/ZDOK1.DP_P15") (class "Default")
      (node (ref "U1") (pin "U36") (pinfunction "IO_L16P_17_U36") (pintype "passive"))
    )
    (net (code "357") (name "/ZDOK1.DP_P16") (class "Default")
      (node (ref "U1") (pin "T41") (pinfunction "IO_L19P_17_T41") (pintype "passive"))
    )
    (net (code "358") (name "/ZDOK1.DP_P17") (class "Default")
      (node (ref "U1") (pin "R39") (pinfunction "IO_L8P_SRCC_17_R39") (pintype "passive"))
    )
    (net (code "359") (name "/ZDOK1.DP_P19") (class "Default")
      (node (ref "U1") (pin "N40") (pinfunction "IO_L11P_SRCC_17_N40") (pintype "passive"))
    )
    (net (code "360") (name "/ZDOK1.DP_P20") (class "Default")
      (node (ref "U1") (pin "AA35") (pinfunction "IO_L8P_SRCC_16_AA35") (pintype "passive"))
    )
    (net (code "361") (name "/ZDOK1.DP_P21") (class "Default")
      (node (ref "U1") (pin "W32") (pinfunction "IO_L9P_MRCC_16_W32") (pintype "passive"))
    )
    (net (code "362") (name "/ZDOK1.DP_P22") (class "Default")
      (node (ref "U1") (pin "W36") (pinfunction "IO_L2P_16_W36") (pintype "passive"))
    )
    (net (code "363") (name "/ZDOK1.DP_P23") (class "Default")
      (node (ref "U1") (pin "V40") (pinfunction "IO_L11P_SRCC_16_V40") (pintype "passive"))
    )
    (net (code "364") (name "/ZDOK1.DP_P24") (class "Default")
      (node (ref "U1") (pin "U37") (pinfunction "IO_L1P_16_U37") (pintype "passive"))
    )
    (net (code "365") (name "/ZDOK1.DP_P25") (class "Default")
      (node (ref "U1") (pin "T39") (pinfunction "IO_L10P_MRCC_17_T39") (pintype "passive"))
    )
    (net (code "366") (name "/ZDOK1.DP_P26") (class "Default")
      (node (ref "U1") (pin "P42") (pinfunction "IO_L15P_17_P42") (pintype "passive"))
    )
    (net (code "367") (name "/ZDOK1.DP_P27") (class "Default")
      (node (ref "U1") (pin "P40") (pinfunction "IO_L13P_17_P40") (pintype "passive"))
    )
    (net (code "368") (name "/ZDOK1.DP_P28") (class "Default")
      (node (ref "U1") (pin "M38") (pinfunction "IO_L2P_17_M38") (pintype "passive"))
    )
    (net (code "369") (name "/ZDOK1.DP_P29") (class "Default")
      (node (ref "U1") (pin "AA36") (pinfunction "IO_L4P_16_AA36") (pintype "passive"))
    )
    (net (code "370") (name "/ZDOK1.DP_P30") (class "Default")
      (node (ref "U1") (pin "W42") (pinfunction "IO_L15P_16_W42") (pintype "passive"))
    )
    (net (code "371") (name "/ZDOK1.DP_P31") (class "Default")
      (node (ref "U1") (pin "Y40") (pinfunction "IO_L17P_16_Y40") (pintype "passive"))
    )
    (net (code "372") (name "/ZDOK1.DP_P32") (class "Default")
      (node (ref "U1") (pin "V38") (pinfunction "IO_L7P_16_V38") (pintype "passive"))
    )
    (net (code "373") (name "/ZDOK1.DP_P33") (class "Default")
      (node (ref "U1") (pin "V34") (pinfunction "IO_L10P_MRCC_16_V34") (pintype "passive"))
    )
    (net (code "374") (name "/ZDOK1.DP_P34") (class "Default")
      (node (ref "U1") (pin "T34") (pinfunction "IO_L18P_17_T34") (pintype "passive"))
    )
    (net (code "375") (name "/ZDOK1.DP_P35") (class "Default")
      (node (ref "U1") (pin "R40") (pinfunction "IO_L17P_17_R40") (pintype "passive"))
    )
    (net (code "376") (name "/ZDOK1.DP_P36") (class "Default")
      (node (ref "U1") (pin "N36") (pinfunction "IO_L6P_17_N36") (pintype "passive"))
    )
    (net (code "377") (name "/ZDOK1.DP_P37") (class "Default")
      (node (ref "U1") (pin "N38") (pinfunction "IO_L5P_17_N38") (pintype "passive"))
    )
    (net (code "384") (name "1V5") (class "Default")
      (node (ref "C363") (pin "1") (pinfunction "1_1") (pintype "passive"))
      (node (ref "C367") (pin "2") (pinfunction "2_2") (pintype "passive"))
      (node (ref "C369") (pin "2") (pinfunction "2_2") (pintype "passive"))
      (node (ref "R317") (pin "2") (pinfunction "2_2") (pintype "passive"))
      (node (ref "U1") (pin "AH22") (pinfunction "VCCO_21_AH22") (pintype "passive"))
      (node (ref "U1") (pin "AL23") (pinfunction "VCCO_21_AL23") (pintype "passive"))
      (node (ref "U1") (pin "AN27") (pinfunction "VCCO_22_AN27") (pintype "passive"))
      (node (ref "U1") (pin "AP24") (pinfunction "VCCO_21_AP24") (pintype "passive"))
      (node (ref "U1") (pin "AT28") (pinfunction "VCCO_22_AT28") (pintype "passive"))
      (node (ref "U1") (pin "AU25") (pinfunction "VCCO_21_AU25") (pintype "passive"))
      (node (ref "U1") (pin "AW29") (pinfunction "VCCO_22_AW29") (pintype "passive"))
      (node (ref "U1") (pin "AY26") (pinfunction "VCCO_21_AY26") (pintype "passive"))
      (node (ref "U1") (pin "BA33") (pinfunction "VCCO_22_BA33") (pintype "passive"))
      (node (ref "U1") (pin "BB30") (pinfunction "VCCO_22_BB30") (pintype "passive"))
    )
    (net (code "385") (name "2V5") (class "Default")
      (node (ref "C361") (pin "1") (pinfunction "1_1") (pintype "passive"))
      (node (ref "C362") (pin "1") (pinfunction "1_1") (pintype "passive"))
      (node (ref "C365") (pin "2") (pinfunction "2_2") (pintype "passive"))
      (node (ref "C366") (pin "2") (pinfunction "2_2") (pintype "passive"))
      (node (ref "C371") (pin "2") (pinfunction "2_2") (pintype "passive"))
      (node (ref "R253") (pin "2") (pinfunction "2_2") (pintype "passive"))
      (node (ref "R254") (pin "2") (pinfunction "2_2") (pintype "passive"))
      (node (ref "R258") (pin "2") (pinfunction "2_2") (pintype "passive"))
      (node (ref "R259") (pin "2") (pinfunction "2_2") (pintype "passive"))
      (node (ref "R260") (pin "2") (pinfunction "2_2") (pintype "passive"))
      (node (ref "R261") (pin "2") (pinfunction "2_2") (pintype "passive"))
      (node (ref "U1") (pin "M10") (pinfunction "VCCO_0_M10") (pintype "passive"))
      (node (ref "U1") (pin "M40") (pinfunction "VCCO_17_M40") (pintype "passive"))
      (node (ref "U1") (pin "N37") (pinfunction "VCCO_17_N37") (pintype "passive"))
      (node (ref "U1") (pin "P34") (pinfunction "VCCO_17_P34") (pintype "passive"))
      (node (ref "U1") (pin "R10") (pinfunction "VBATT_0_R10") (pintype "passive"))
      (node (ref "U1") (pin "R11") (pinfunction "VCCO_0_R11") (pintype "passive"))
      (node (ref "U1") (pin "R41") (pinfunction "VCCO_17_R41") (pintype "passive"))
      (node (ref "U1") (pin "T38") (pinfunction "VCCO_17_T38") (pintype "passive"))
      (node (ref "U1") (pin "U35") (pinfunction "VCCO_16_U35") (pintype "passive"))
      (node (ref "U1") (pin "V32") (pinfunction "VCCO_16_V32") (pintype "passive"))
      (node (ref "U1") (pin "V42") (pinfunction "VCCO_16_V42") (pintype "passive"))
      (node (ref "U1") (pin "W39") (pinfunction "VCCO_16_W39") (pintype "passive"))
      (node (ref "U1") (pin "Y22") (pinfunction "AVDD_0_Y22") (pintype "passive"))
      (node (ref "U1") (pin "Y36") (pinfunction "VCCO_16_Y36") (pintype "passive"))
      (node (ref "U51") (pin "5") (pinfunction "VCC_5") (pintype "passive"))
    )
    (net (code "386") (name "3V3AUX") (class "Default")
      (node (ref "R257") (pin "2") (pinfunction "2_2") (pintype "passive"))
    )
    (net (code "387") (name "GND") (class "Default")
      (node (ref "C361") (pin "2") (pinfunction "2_2") (pintype "passive"))
      (node (ref "C362") (pin "2") (pinfunction "2_2") (pintype "passive"))
      (node (ref "C363") (pin "2") (pinfunction "2_2") (pintype "passive"))
      (node (ref "C365") (pin "1") (pinfunction "1_1") (pintype "passive"))
      (node (ref "C366") (pin "1") (pinfunction "1_1") (pintype "passive"))
      (node (ref "C367") (pin "1") (pinfunction "1_1") (pintype "passive"))
      (node (ref "C368") (pin "1") (pinfunction "1_1") (pintype "passive"))
      (node (ref "C369") (pin "1") (pinfunction "1_1") (pintype "passive"))
      (node (ref "C371") (pin "1") (pinfunction "1_1") (pintype "passive"))
      (node (ref "R255") (pin "2") (pinfunction "2_2") (pintype "passive"))
      (node (ref "R256") (pin "1") (pinfunction "1_1") (pintype "passive"))
      (node (ref "R263") (pin "1") (pinfunction "1_1") (pintype "passive"))
      (node (ref "R300") (pin "2") (pinfunction "2_2") (pintype "passive"))
      (node (ref "R318") (pin "1") (pinfunction "1_1") (pintype "passive"))
      (node (ref "R334") (pin "2") (pinfunction "2_2") (pintype "passive"))
      (node (ref "R335") (pin "2") (pinfunction "2_2") (pintype "passive"))
      (node (ref "U1") (pin "AA21") (pinfunction "VREFN_0_AA21") (pintype "passive"))
      (node (ref "U1") (pin "AA22") (pinfunction "VP_0_AA22") (pintype "passive"))
      (node (ref "U1") (pin "AB21") (pinfunction "VN_0_AB21") (pintype "passive"))
      (node (ref "U1") (pin "AB22") (pinfunction "VREFP_0_AB22") (pintype "passive"))
      (node (ref "U1") (pin "Y21") (pinfunction "AVSS_0_Y21") (pintype "passive"))
      (node (ref "U51") (pin "3") (pinfunction "GND_3") (pintype "passive"))
    )
    (net (code "388") (name "Net-(U1A-VFS_0)") (class "Default")
      (node (ref "R255") (pin "1") (pinfunction "1_1") (pintype "passive"))
      (node (ref "U1") (pin "AH10") (pinfunction "VFS_0_AH10") (pintype "passive"))
    )
    (net (code "389") (name "Net-(U1H-IO_L12N_VRP_21)") (class "Default")
      (node (ref "R318") (pin "2") (pinfunction "2_2") (pintype "passive"))
      (node (ref "U1") (pin "AV25") (pinfunction "IO_L12N_VRP_21_AV25") (pintype "passive"))
    )
    (net (code "390") (name "Net-(U1H-IO_L12P_VRN_21)") (class "Default")
      (node (ref "R317") (pin "1") (pinfunction "1_1") (pintype "passive"))
      (node (ref "U1") (pin "AV24") (pinfunction "IO_L12P_VRN_21_AV24") (pintype "passive"))
    )
    (net (code "391") (name "Net-(U51-A)") (class "Default")
      (node (ref "R257") (pin "1") (pinfunction "1_1") (pintype "passive"))
      (node (ref "R262") (pin "2") (pinfunction "2_2") (pintype "passive"))
      (node (ref "U51") (pin "1") (pinfunction "A_1") (pintype "passive"))
    )
    (net (code "392") (name "QDR23_VREF") (class "Default")
      (node (ref "C368") (pin "2") (pinfunction "2_2") (pintype "passive"))
      (node (ref "U1") (pin "AY25") (pinfunction "IO_L14N_VREF_21_AY25") (pintype "passive"))
      (node (ref "U1") (pin "BA27") (pinfunction "IO_L4N_VREF_21_BA27") (pintype "passive"))
    )
    (net (code "393") (name "unconnected-(U1I-IO_L4N_VREF_22-PadAW32)") (class "Default")
      (node (ref "U1") (pin "AW32") (pinfunction "IO_L4N_VREF_22_AW32") (pintype "passive+no_connect"))
    )
    (net (code "394") (name "unconnected-(U1I-IO_L8P_SRCC_22-PadBA30)") (class "Default")
      (node (ref "U1") (pin "BA30") (pinfunction "IO_L8P_SRCC_22_BA30") (pintype "passive+no_connect"))
    )
    (net (code "395") (name "unconnected-(U1I-IO_L9P_MRCC_22-PadAM26)") (class "Default")
      (node (ref "U1") (pin "AM26") (pinfunction "IO_L9P_MRCC_22_AM26") (pintype "passive+no_connect"))
    )
    (net (code "396") (name "unconnected-(U1I-IO_L10P_MRCC_22-PadAN28)") (class "Default")
      (node (ref "U1") (pin "AN28") (pinfunction "IO_L10P_MRCC_22_AN28") (pintype "passive+no_connect"))
    )
    (net (code "397") (name "unconnected-(U1I-IO_L14N_VREF_22-PadBB32)") (class "Default")
      (node (ref "U1") (pin "BB32") (pinfunction "IO_L14N_VREF_22_BB32") (pintype "passive+no_connect"))
    )
  )
)
